# SPL_1_0.net
KiCad netlist of a schematic drawn in EAGLE
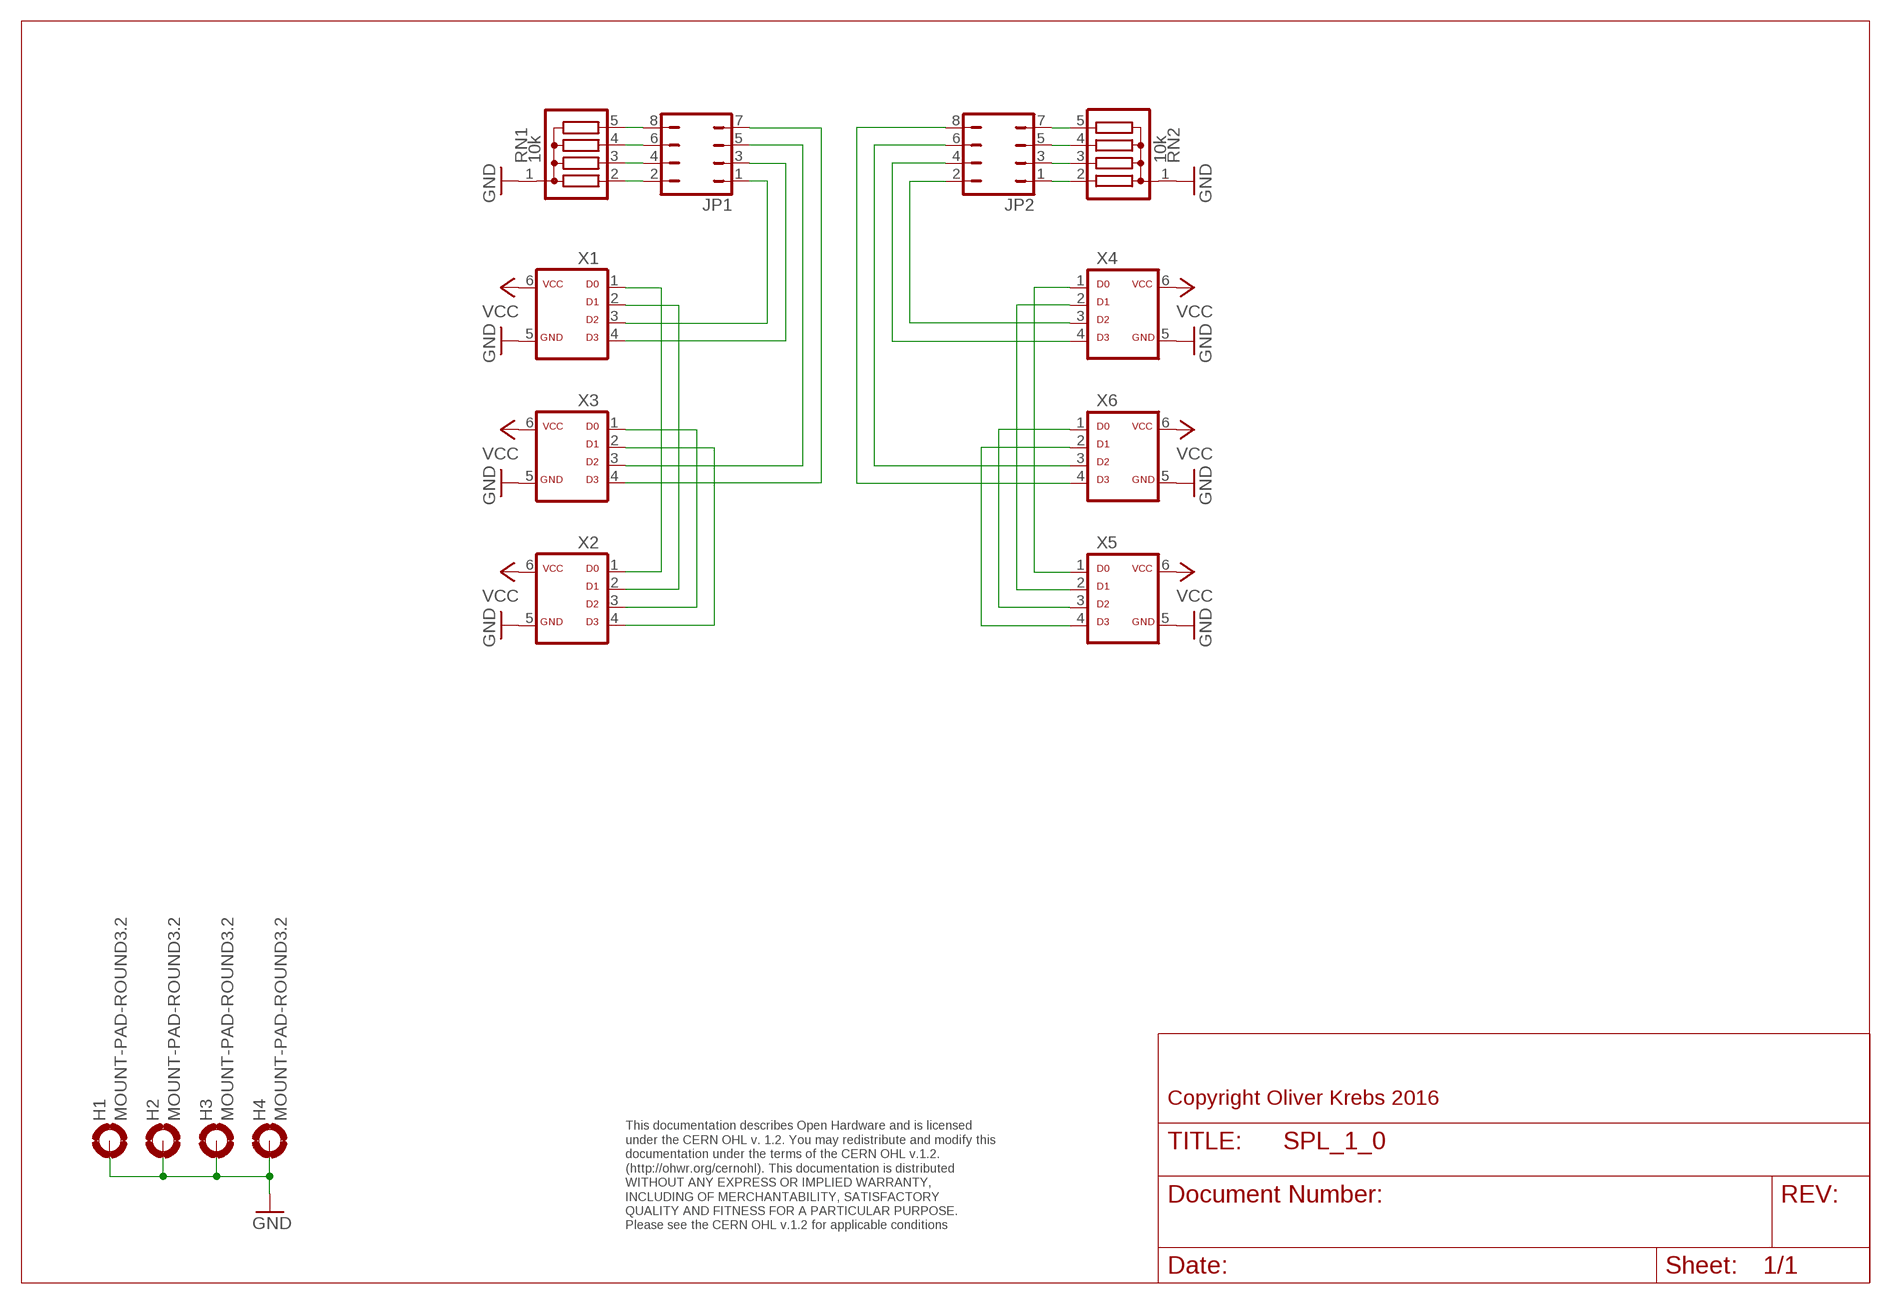
[diagram p0: schematic, sheet 1]

(export (version "E")
  (design (tool "Eeschema 10.0.6"))
  (components
    (comp (ref "H1")
      (value "MOUNT-PAD-ROUND3.2")
      (footprint "eagle-import:3,2-PAD")
      (libsource (lib "eagle-import") (part "MOUNT-PAD-ROUND3.2"))
    )
    (comp (ref "H2")
      (value "MOUNT-PAD-ROUND3.2")
      (footprint "eagle-import:3,2-PAD")
      (libsource (lib "eagle-import") (part "MOUNT-PAD-ROUND3.2"))
    )
    (comp (ref "H3")
      (value "MOUNT-PAD-ROUND3.2")
      (footprint "eagle-import:3,2-PAD")
      (libsource (lib "eagle-import") (part "MOUNT-PAD-ROUND3.2"))
    )
    (comp (ref "H4")
      (value "MOUNT-PAD-ROUND3.2")
      (footprint "eagle-import:3,2-PAD")
      (libsource (lib "eagle-import") (part "MOUNT-PAD-ROUND3.2"))
    )
    (comp (ref "JP1")
      (value "JP4Q")
      (footprint "eagle-import:JP4Q")
      (libsource (lib "eagle-import") (part "JP4Q"))
    )
    (comp (ref "JP2")
      (value "JP4Q")
      (footprint "eagle-import:JP4Q")
      (libsource (lib "eagle-import") (part "JP4Q"))
    )
    (comp (ref "RN1")
      (value "10k")
      (footprint "eagle-import:SIL5")
      (libsource (lib "eagle-import") (part "G04R"))
    )
    (comp (ref "RN2")
      (value "10k")
      (footprint "eagle-import:SIL5")
      (libsource (lib "eagle-import") (part "G04R"))
    )
    (comp (ref "X1")
      (value "ML6D")
      (footprint "eagle-import:ML-6")
      (libsource (lib "eagle-import") (part "ML6D"))
    )
    (comp (ref "X2")
      (value "ML6D")
      (footprint "eagle-import:ML-6")
      (libsource (lib "eagle-import") (part "ML6D"))
    )
    (comp (ref "X3")
      (value "ML6D")
      (footprint "eagle-import:ML-6")
      (libsource (lib "eagle-import") (part "ML6D"))
    )
    (comp (ref "X4")
      (value "ML6D")
      (footprint "eagle-import:ML-6")
      (libsource (lib "eagle-import") (part "ML6D"))
    )
    (comp (ref "X5")
      (value "ML6D")
      (footprint "eagle-import:ML-6")
      (libsource (lib "eagle-import") (part "ML6D"))
    )
    (comp (ref "X6")
      (value "ML6D")
      (footprint "eagle-import:ML-6")
      (libsource (lib "eagle-import") (part "ML6D"))
    )
  )
  (nets
    (net (code "1") (name "GND") (class "Default")
      (node (ref "H1") (pin "B3,2") (pinfunction "MOUNT_B3,2") (pintype "passive"))
      (node (ref "H2") (pin "B3,2") (pinfunction "MOUNT_B3,2") (pintype "passive"))
      (node (ref "H3") (pin "B3,2") (pinfunction "MOUNT_B3,2") (pintype "passive"))
      (node (ref "H4") (pin "B3,2") (pinfunction "MOUNT_B3,2") (pintype "passive"))
      (node (ref "RN1") (pin "1") (pinfunction "1_1") (pintype "passive"))
      (node (ref "RN2") (pin "1") (pinfunction "1_1") (pintype "passive"))
      (node (ref "X1") (pin "5") (pinfunction "5_5") (pintype "passive"))
      (node (ref "X2") (pin "5") (pinfunction "5_5") (pintype "passive"))
      (node (ref "X3") (pin "5") (pinfunction "5_5") (pintype "passive"))
      (node (ref "X4") (pin "5") (pinfunction "5_5") (pintype "passive"))
      (node (ref "X5") (pin "5") (pinfunction "5_5") (pintype "passive"))
      (node (ref "X6") (pin "5") (pinfunction "5_5") (pintype "passive"))
    )
    (net (code "2") (name "Net-(JP1-Pad1)") (class "Default")
      (node (ref "JP1") (pin "1") (pinfunction "1_1") (pintype "passive"))
      (node (ref "X1") (pin "3") (pinfunction "3_3") (pintype "passive"))
    )
    (net (code "3") (name "Net-(JP1-Pad2)") (class "Default")
      (node (ref "JP1") (pin "2") (pinfunction "2_2") (pintype "passive"))
      (node (ref "RN1") (pin "2") (pinfunction "2_2") (pintype "passive"))
    )
    (net (code "4") (name "Net-(JP1-Pad3)") (class "Default")
      (node (ref "JP1") (pin "3") (pinfunction "3_3") (pintype "passive"))
      (node (ref "X1") (pin "4") (pinfunction "4_4") (pintype "passive"))
    )
    (net (code "5") (name "Net-(JP1-Pad4)") (class "Default")
      (node (ref "JP1") (pin "4") (pinfunction "4_4") (pintype "passive"))
      (node (ref "RN1") (pin "3") (pinfunction "3_3") (pintype "passive"))
    )
    (net (code "6") (name "Net-(JP1-Pad5)") (class "Default")
      (node (ref "JP1") (pin "5") (pinfunction "5_5") (pintype "passive"))
      (node (ref "X3") (pin "3") (pinfunction "3_3") (pintype "passive"))
    )
    (net (code "7") (name "Net-(JP1-Pad6)") (class "Default")
      (node (ref "JP1") (pin "6") (pinfunction "6_6") (pintype "passive"))
      (node (ref "RN1") (pin "4") (pinfunction "4_4") (pintype "passive"))
    )
    (net (code "8") (name "Net-(JP1-Pad7)") (class "Default")
      (node (ref "JP1") (pin "7") (pinfunction "7_7") (pintype "passive"))
      (node (ref "X3") (pin "4") (pinfunction "4_4") (pintype "passive"))
    )
    (net (code "9") (name "Net-(JP1-Pad8)") (class "Default")
      (node (ref "JP1") (pin "8") (pinfunction "8_8") (pintype "passive"))
      (node (ref "RN1") (pin "5") (pinfunction "5_5") (pintype "passive"))
    )
    (net (code "10") (name "Net-(JP2-Pad1)") (class "Default")
      (node (ref "JP2") (pin "1") (pinfunction "1_1") (pintype "passive"))
      (node (ref "RN2") (pin "2") (pinfunction "2_2") (pintype "passive"))
    )
    (net (code "11") (name "Net-(JP2-Pad2)") (class "Default")
      (node (ref "JP2") (pin "2") (pinfunction "2_2") (pintype "passive"))
      (node (ref "X4") (pin "3") (pinfunction "3_3") (pintype "passive"))
    )
    (net (code "12") (name "Net-(JP2-Pad3)") (class "Default")
      (node (ref "JP2") (pin "3") (pinfunction "3_3") (pintype "passive"))
      (node (ref "RN2") (pin "3") (pinfunction "3_3") (pintype "passive"))
    )
    (net (code "13") (name "Net-(JP2-Pad4)") (class "Default")
      (node (ref "JP2") (pin "4") (pinfunction "4_4") (pintype "passive"))
      (node (ref "X4") (pin "4") (pinfunction "4_4") (pintype "passive"))
    )
    (net (code "14") (name "Net-(JP2-Pad5)") (class "Default")
      (node (ref "JP2") (pin "5") (pinfunction "5_5") (pintype "passive"))
      (node (ref "RN2") (pin "4") (pinfunction "4_4") (pintype "passive"))
    )
    (net (code "15") (name "Net-(JP2-Pad6)") (class "Default")
      (node (ref "JP2") (pin "6") (pinfunction "6_6") (pintype "passive"))
      (node (ref "X6") (pin "3") (pinfunction "3_3") (pintype "passive"))
    )
    (net (code "16") (name "Net-(JP2-Pad7)") (class "Default")
      (node (ref "JP2") (pin "7") (pinfunction "7_7") (pintype "passive"))
      (node (ref "RN2") (pin "5") (pinfunction "5_5") (pintype "passive"))
    )
    (net (code "17") (name "Net-(JP2-Pad8)") (class "Default")
      (node (ref "JP2") (pin "8") (pinfunction "8_8") (pintype "passive"))
      (node (ref "X6") (pin "4") (pinfunction "4_4") (pintype "passive"))
    )
    (net (code "18") (name "Net-(X1-Pad1)") (class "Default")
      (node (ref "X1") (pin "1") (pinfunction "1_1") (pintype "passive"))
      (node (ref "X2") (pin "1") (pinfunction "1_1") (pintype "passive"))
    )
    (net (code "19") (name "Net-(X1-Pad2)") (class "Default")
      (node (ref "X1") (pin "2") (pinfunction "2_2") (pintype "passive"))
      (node (ref "X2") (pin "2") (pinfunction "2_2") (pintype "passive"))
    )
    (net (code "20") (name "Net-(X2-Pad3)") (class "Default")
      (node (ref "X2") (pin "3") (pinfunction "3_3") (pintype "passive"))
      (node (ref "X3") (pin "1") (pinfunction "1_1") (pintype "passive"))
    )
    (net (code "21") (name "Net-(X2-Pad4)") (class "Default")
      (node (ref "X2") (pin "4") (pinfunction "4_4") (pintype "passive"))
      (node (ref "X3") (pin "2") (pinfunction "2_2") (pintype "passive"))
    )
    (net (code "22") (name "Net-(X4-Pad1)") (class "Default")
      (node (ref "X4") (pin "1") (pinfunction "1_1") (pintype "passive"))
      (node (ref "X5") (pin "1") (pinfunction "1_1") (pintype "passive"))
    )
    (net (code "23") (name "Net-(X4-Pad2)") (class "Default")
      (node (ref "X4") (pin "2") (pinfunction "2_2") (pintype "passive"))
      (node (ref "X5") (pin "2") (pinfunction "2_2") (pintype "passive"))
    )
    (net (code "24") (name "Net-(X5-Pad3)") (class "Default")
      (node (ref "X5") (pin "3") (pinfunction "3_3") (pintype "passive"))
      (node (ref "X6") (pin "1") (pinfunction "1_1") (pintype "passive"))
    )
    (net (code "25") (name "Net-(X5-Pad4)") (class "Default")
      (node (ref "X5") (pin "4") (pinfunction "4_4") (pintype "passive"))
      (node (ref "X6") (pin "2") (pinfunction "2_2") (pintype "passive"))
    )
    (net (code "26") (name "VCC") (class "Default")
      (node (ref "X1") (pin "6") (pinfunction "6_6") (pintype "passive"))
      (node (ref "X2") (pin "6") (pinfunction "6_6") (pintype "passive"))
      (node (ref "X3") (pin "6") (pinfunction "6_6") (pintype "passive"))
      (node (ref "X4") (pin "6") (pinfunction "6_6") (pintype "passive"))
      (node (ref "X5") (pin "6") (pinfunction "6_6") (pintype "passive"))
      (node (ref "X6") (pin "6") (pinfunction "6_6") (pintype "passive"))
    )
  )
)
